# SDMMC.net
KiCad netlist of a schematic drawn in Altium Designer
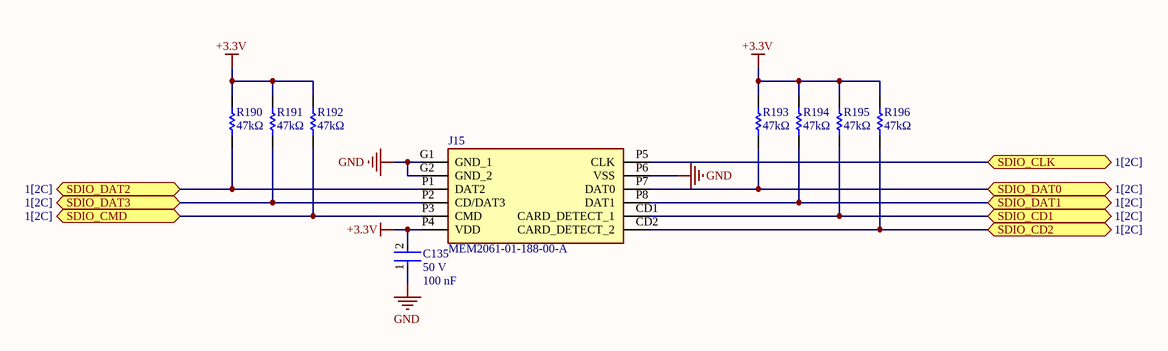
[diagram p0: SDMMC.SchDoc]

(export (version "E")
  (design (tool "Eeschema 10.0.6"))
  (components
    (comp (ref "C135")
      (value "100 nF")
      (footprint "FP-C0603C-CF-IPC_B")
      (description "CAP CER 0.1UF 50V 20% X7R 0603")
      (fields
        (field (name "VOLTAGE RATING") "50 V")
        (field (name "MANUFACTURER PART NUMBER") "C0603C104M5RACTU")
        (field (name "MANUFACTURER") "KEMET")
      )
      (libsource (lib "Altium Content Vault") (part "b4654b650e69147ec39a6b967a45e02"))
    )
    (comp (ref "J15")
      (value "MEM2061-01-188-00-A")
      (footprint "SamacSys:MEM20610118800A")
      (description "Connector")
      (fields (field (name "MOUSER PART NUMBER") "640-MEM20610118800A"))
      (libsource (lib "*") (part "MEM2061-01-188-00-A"))
    )
    (comp (ref "R190")
      (value "RC0603FR-1347KL")
      (footprint "RESC1608X55X25ML10T15")
      (fields (field (name "MANUFACTURER") "Yageo") (field (name "RESISTANCE") "47kΩ"))
      (libsource (lib "Altium Content Vault") (part "RES"))
    )
    (comp (ref "R191")
      (value "RC0603FR-1347KL")
      (footprint "RESC1608X55X25ML10T15")
      (fields (field (name "MANUFACTURER") "Yageo") (field (name "RESISTANCE") "47kΩ"))
      (libsource (lib "Altium Content Vault") (part "RES"))
    )
    (comp (ref "R192")
      (value "RC0603FR-1347KL")
      (footprint "RESC1608X55X25ML10T15")
      (fields (field (name "MANUFACTURER") "Yageo") (field (name "RESISTANCE") "47kΩ"))
      (libsource (lib "Altium Content Vault") (part "RES"))
    )
    (comp (ref "R193")
      (value "RC0603FR-1347KL")
      (footprint "RESC1608X55X25ML10T15")
      (fields (field (name "MANUFACTURER") "Yageo") (field (name "RESISTANCE") "47kΩ"))
      (libsource (lib "Altium Content Vault") (part "RES"))
    )
    (comp (ref "R194")
      (value "RC0603FR-1347KL")
      (footprint "RESC1608X55X25ML10T15")
      (fields (field (name "MANUFACTURER") "Yageo") (field (name "RESISTANCE") "47kΩ"))
      (libsource (lib "Altium Content Vault") (part "RES"))
    )
    (comp (ref "R195")
      (value "RC0603FR-1347KL")
      (footprint "RESC1608X55X25ML10T15")
      (fields (field (name "MANUFACTURER") "Yageo") (field (name "RESISTANCE") "47kΩ"))
      (libsource (lib "Altium Content Vault") (part "RES"))
    )
    (comp (ref "R196")
      (value "RC0603FR-1347KL")
      (footprint "RESC1608X55X25ML10T15")
      (fields (field (name "MANUFACTURER") "Yageo") (field (name "RESISTANCE") "47kΩ"))
      (libsource (lib "Altium Content Vault") (part "RES"))
    )
  )
  (nets
    (net (code "1") (name "+3.3V") (class "Default")
      (node (ref "C135") (pin "2") (pinfunction "2_2") (pintype "passive"))
      (node (ref "J15") (pin "P4") (pinfunction "VDD_P4") (pintype "passive"))
      (node (ref "R190") (pin "2") (pinfunction "2_2") (pintype "passive"))
      (node (ref "R191") (pin "2") (pinfunction "2_2") (pintype "passive"))
      (node (ref "R192") (pin "2") (pinfunction "2_2") (pintype "passive"))
      (node (ref "R193") (pin "2") (pinfunction "2_2") (pintype "passive"))
      (node (ref "R194") (pin "2") (pinfunction "2_2") (pintype "passive"))
      (node (ref "R195") (pin "2") (pinfunction "2_2") (pintype "passive"))
      (node (ref "R196") (pin "2") (pinfunction "2_2") (pintype "passive"))
    )
    (net (code "2") (name "/SDIO_CD1") (class "Default")
      (node (ref "J15") (pin "CD1") (pinfunction "CARD_DETECT_1_CD1") (pintype "passive"))
      (node (ref "R195") (pin "1") (pinfunction "1_1") (pintype "passive"))
    )
    (net (code "3") (name "/SDIO_CD2") (class "Default")
      (node (ref "J15") (pin "CD2") (pinfunction "CARD_DETECT_2_CD2") (pintype "passive"))
      (node (ref "R196") (pin "1") (pinfunction "1_1") (pintype "passive"))
    )
    (net (code "4") (name "/SDIO_CLK") (class "Default")
      (node (ref "J15") (pin "P5") (pinfunction "CLK_P5") (pintype "passive"))
    )
    (net (code "5") (name "/SDIO_CMD") (class "Default")
      (node (ref "J15") (pin "P3") (pinfunction "CMD_P3") (pintype "passive"))
      (node (ref "R192") (pin "1") (pinfunction "1_1") (pintype "passive"))
    )
    (net (code "6") (name "/SDIO_DAT0") (class "Default")
      (node (ref "J15") (pin "P7") (pinfunction "DAT0_P7") (pintype "passive"))
      (node (ref "R193") (pin "1") (pinfunction "1_1") (pintype "passive"))
    )
    (net (code "7") (name "/SDIO_DAT1") (class "Default")
      (node (ref "J15") (pin "P8") (pinfunction "DAT1_P8") (pintype "passive"))
      (node (ref "R194") (pin "1") (pinfunction "1_1") (pintype "passive"))
    )
    (net (code "8") (name "/SDIO_DAT2") (class "Default")
      (node (ref "J15") (pin "P1") (pinfunction "DAT2_P1") (pintype "passive"))
      (node (ref "R190") (pin "1") (pinfunction "1_1") (pintype "passive"))
    )
    (net (code "9") (name "/SDIO_DAT3") (class "Default")
      (node (ref "J15") (pin "P2") (pinfunction "CD/DAT3_P2") (pintype "passive"))
      (node (ref "R191") (pin "1") (pinfunction "1_1") (pintype "passive"))
    )
    (net (code "10") (name "GND") (class "Default")
      (node (ref "C135") (pin "1") (pinfunction "1_1") (pintype "passive"))
      (node (ref "J15") (pin "G1") (pinfunction "GND_1_G1") (pintype "passive"))
      (node (ref "J15") (pin "G2") (pinfunction "GND_2_G2") (pintype "passive"))
      (node (ref "J15") (pin "P6") (pinfunction "VSS_P6") (pintype "passive"))
    )
  )
)
